# BMW_E34_Touring_Bagage_Light.net
KiCad netlist of a schematic drawn in Altium Designer
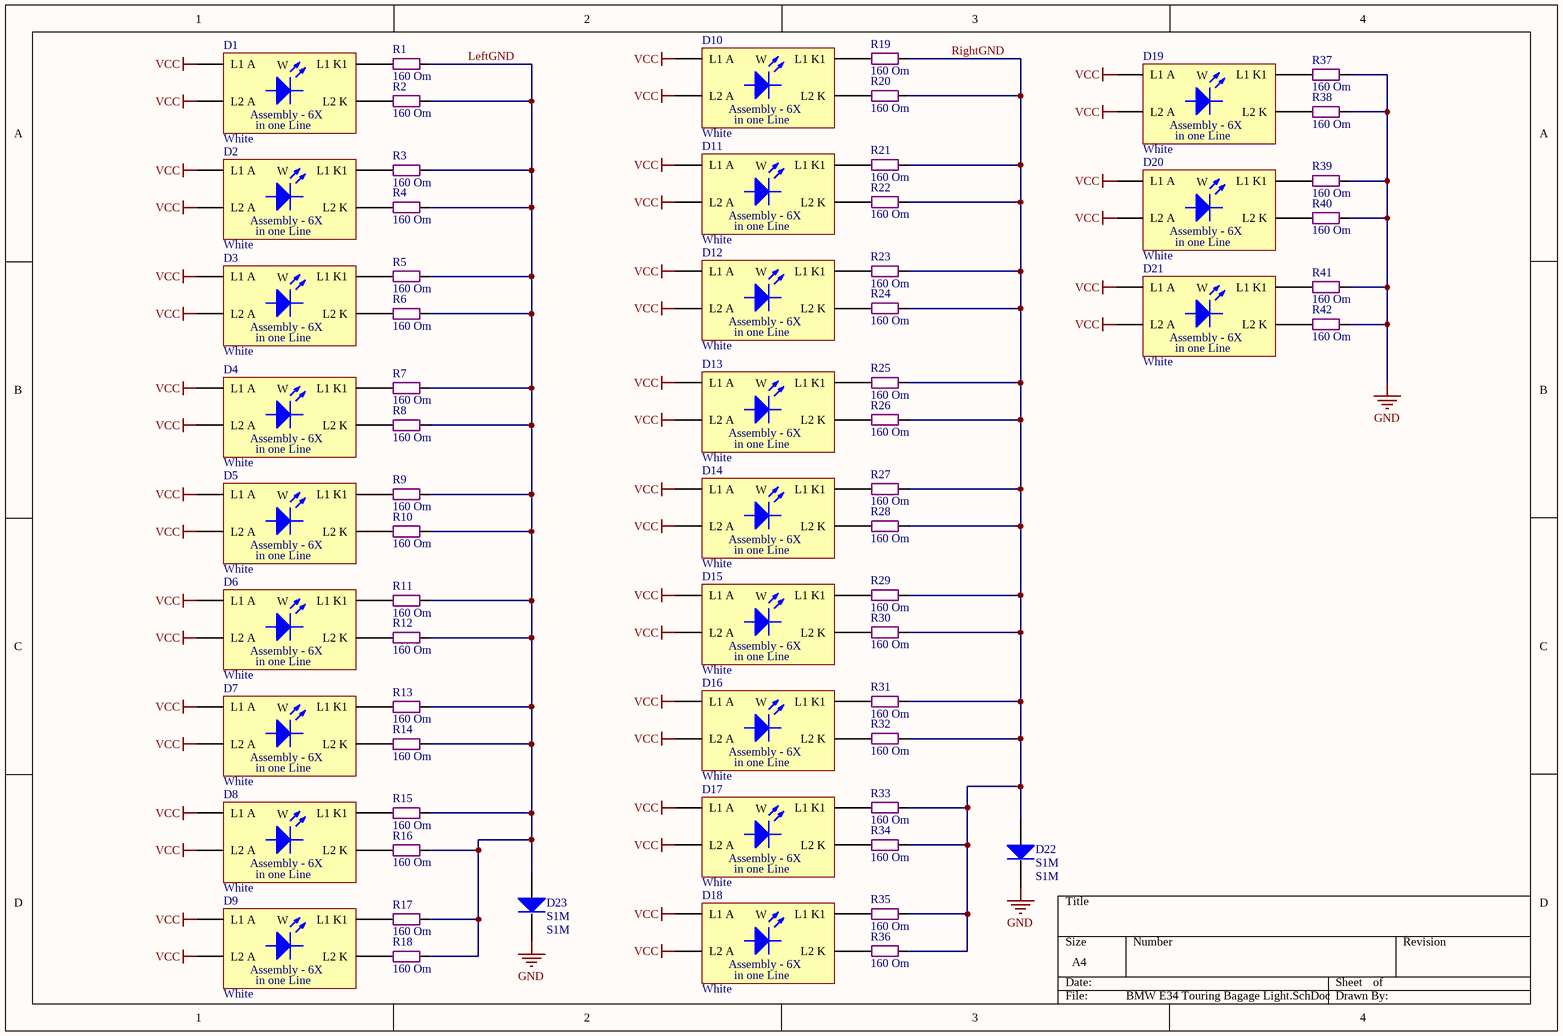
[diagram p0: BMW E34 Touring Bagage Light.SchDoc]

(export (version "E")
  (design (tool "Eeschema 10.0.6"))
  (components
    (comp (ref "D1")
      (value "White")
      (footprint "LED:LED Assembly Round 5mm White 6X 0.5mm")
      (description "3.2-3.4v 25mA, 16-20cd")
      (libsource (lib "LED") (part "Led Assembly Round 5mm White 6X"))
    )
    (comp (ref "D2")
      (value "White")
      (footprint "LED:LED Assembly Round 5mm White 6X 0.5mm")
      (description "3.2-3.4v 25mA, 16-20cd")
      (libsource (lib "LED") (part "Led Assembly Round 5mm White 6X"))
    )
    (comp (ref "D3")
      (value "White")
      (footprint "LED:LED Assembly Round 5mm White 6X 0.5mm")
      (description "3.2-3.4v 25mA, 16-20cd")
      (libsource (lib "LED") (part "Led Assembly Round 5mm White 6X"))
    )
    (comp (ref "D4")
      (value "White")
      (footprint "LED:LED Assembly Round 5mm White 6X 0.5mm")
      (description "3.2-3.4v 25mA, 16-20cd")
      (libsource (lib "LED") (part "Led Assembly Round 5mm White 6X"))
    )
    (comp (ref "D5")
      (value "White")
      (footprint "LED:LED Assembly Round 5mm White 6X")
      (description "3.2-3.4v 25mA, 16-20cd")
      (libsource (lib "LED") (part "Led Assembly Round 5mm White 6X"))
    )
    (comp (ref "D6")
      (value "White")
      (footprint "LED:LED Assembly Round 5mm White 6X")
      (description "3.2-3.4v 25mA, 16-20cd")
      (libsource (lib "LED") (part "Led Assembly Round 5mm White 6X"))
    )
    (comp (ref "D7")
      (value "White")
      (footprint "LED:LED Assembly Round 5mm White 6X 0.5mm")
      (description "3.2-3.4v 25mA, 16-20cd")
      (libsource (lib "LED") (part "Led Assembly Round 5mm White 6X"))
    )
    (comp (ref "D8")
      (value "White")
      (footprint "LED:LED Assembly Round 5mm White 6X 0.5mm")
      (description "3.2-3.4v 25mA, 16-20cd")
      (libsource (lib "LED") (part "Led Assembly Round 5mm White 6X"))
    )
    (comp (ref "D9")
      (value "White")
      (footprint "LED:LED Assembly Round 5mm White 6X 0.5mm")
      (description "3.2-3.4v 25mA, 16-20cd")
      (libsource (lib "LED") (part "Led Assembly Round 5mm White 6X"))
    )
    (comp (ref "D10")
      (value "White")
      (footprint "LED:LED Assembly Round 5mm White 6X 0.5mm")
      (description "3.2-3.4v 25mA, 16-20cd")
      (libsource (lib "LED") (part "Led Assembly Round 5mm White 6X"))
    )
    (comp (ref "D11")
      (value "White")
      (footprint "LED:LED Assembly Round 5mm White 6X 0.5mm")
      (description "3.2-3.4v 25mA, 16-20cd")
      (libsource (lib "LED") (part "Led Assembly Round 5mm White 6X"))
    )
    (comp (ref "D12")
      (value "White")
      (footprint "LED:LED Assembly Round 5mm White 6X 0.5mm")
      (description "3.2-3.4v 25mA, 16-20cd")
      (libsource (lib "LED") (part "Led Assembly Round 5mm White 6X"))
    )
    (comp (ref "D13")
      (value "White")
      (footprint "LED:LED Assembly Round 5mm White 6X")
      (description "3.2-3.4v 25mA, 16-20cd")
      (libsource (lib "LED") (part "Led Assembly Round 5mm White 6X"))
    )
    (comp (ref "D14")
      (value "White")
      (footprint "LED:LED Assembly Round 5mm White 6X")
      (description "3.2-3.4v 25mA, 16-20cd")
      (libsource (lib "LED") (part "Led Assembly Round 5mm White 6X"))
    )
    (comp (ref "D15")
      (value "White")
      (footprint "LED:LED Assembly Round 5mm White 6X 0.5mm")
      (description "3.2-3.4v 25mA, 16-20cd")
      (libsource (lib "LED") (part "Led Assembly Round 5mm White 6X"))
    )
    (comp (ref "D16")
      (value "White")
      (footprint "LED:LED Assembly Round 5mm White 6X 0.5mm")
      (description "3.2-3.4v 25mA, 16-20cd")
      (libsource (lib "LED") (part "Led Assembly Round 5mm White 6X"))
    )
    (comp (ref "D17")
      (value "White")
      (footprint "LED:LED Assembly Round 5mm White 6X 0.5mm")
      (description "3.2-3.4v 25mA, 16-20cd")
      (libsource (lib "LED") (part "Led Assembly Round 5mm White 6X"))
    )
    (comp (ref "D18")
      (value "White")
      (footprint "LED:LED Assembly Round 5mm White 6X 0.5mm")
      (description "3.2-3.4v 25mA, 16-20cd")
      (libsource (lib "LED") (part "Led Assembly Round 5mm White 6X"))
    )
    (comp (ref "D19")
      (value "White")
      (footprint "LED:LED Assembly Round 5mm White 2X3 1mm")
      (description "3.2-3.4v 25mA, 16-20cd")
      (libsource (lib "LED") (part "Led Assembly Round 5mm White 6X"))
    )
    (comp (ref "D20")
      (value "White")
      (footprint "LED:LED Assembly Round 5mm White 2X3 1mm")
      (description "3.2-3.4v 25mA, 16-20cd")
      (libsource (lib "LED") (part "Led Assembly Round 5mm White 6X"))
    )
    (comp (ref "D21")
      (value "White")
      (footprint "LED:LED Assembly Round 5mm White 2X3 1mm")
      (description "3.2-3.4v 25mA, 16-20cd")
      (libsource (lib "LED") (part "Led Assembly Round 5mm White 6X"))
    )
    (comp (ref "D22")
      (value "S1M")
      (footprint "Diodes:DO-214AC")
      (description "1 Amp General Purpose Rectifier")
      (fields (field (name "ALTIUM_VALUE") "S1M"))
      (libsource (lib "Diodes") (part "Diode S1M"))
    )
    (comp (ref "D23")
      (value "S1M")
      (footprint "Diodes:DO-214AC")
      (description "1 Amp General Purpose Rectifier")
      (fields (field (name "ALTIUM_VALUE") "S1M"))
      (libsource (lib "Diodes") (part "Diode S1M"))
    )
    (comp (ref "R1")
      (value "160 Om")
      (footprint "PassiveComponents:SMD 0603 (1608)")
      (libsource (lib "PassiveComponents") (part "Res SMD 0603"))
    )
    (comp (ref "R2")
      (value "160 Om")
      (footprint "PassiveComponents:SMD 0603 (1608)")
      (libsource (lib "PassiveComponents") (part "Res SMD 0603"))
    )
    (comp (ref "R3")
      (value "160 Om")
      (footprint "PassiveComponents:SMD 0603 (1608)")
      (libsource (lib "PassiveComponents") (part "Res SMD 0603"))
    )
    (comp (ref "R4")
      (value "160 Om")
      (footprint "PassiveComponents:SMD 0603 (1608)")
      (libsource (lib "PassiveComponents") (part "Res SMD 0603"))
    )
    (comp (ref "R5")
      (value "160 Om")
      (footprint "PassiveComponents:SMD 0603 (1608)")
      (libsource (lib "PassiveComponents") (part "Res SMD 0603"))
    )
    (comp (ref "R6")
      (value "160 Om")
      (footprint "PassiveComponents:SMD 0603 (1608)")
      (libsource (lib "PassiveComponents") (part "Res SMD 0603"))
    )
    (comp (ref "R7")
      (value "160 Om")
      (footprint "PassiveComponents:SMD 0603 (1608)")
      (libsource (lib "PassiveComponents") (part "Res SMD 0603"))
    )
    (comp (ref "R8")
      (value "160 Om")
      (footprint "PassiveComponents:SMD 0603 (1608)")
      (libsource (lib "PassiveComponents") (part "Res SMD 0603"))
    )
    (comp (ref "R9")
      (value "160 Om")
      (footprint "PassiveComponents:SMD 0603 (1608)")
      (libsource (lib "PassiveComponents") (part "Res SMD 0603"))
    )
    (comp (ref "R10")
      (value "160 Om")
      (footprint "PassiveComponents:SMD 0603 (1608)")
      (libsource (lib "PassiveComponents") (part "Res SMD 0603"))
    )
    (comp (ref "R11")
      (value "160 Om")
      (footprint "PassiveComponents:SMD 0603 (1608)")
      (libsource (lib "PassiveComponents") (part "Res SMD 0603"))
    )
    (comp (ref "R12")
      (value "160 Om")
      (footprint "PassiveComponents:SMD 0603 (1608)")
      (libsource (lib "PassiveComponents") (part "Res SMD 0603"))
    )
    (comp (ref "R13")
      (value "160 Om")
      (footprint "PassiveComponents:SMD 0603 (1608)")
      (libsource (lib "PassiveComponents") (part "Res SMD 0603"))
    )
    (comp (ref "R14")
      (value "160 Om")
      (footprint "PassiveComponents:SMD 0603 (1608)")
      (libsource (lib "PassiveComponents") (part "Res SMD 0603"))
    )
    (comp (ref "R15")
      (value "160 Om")
      (footprint "PassiveComponents:SMD 0603 (1608)")
      (libsource (lib "PassiveComponents") (part "Res SMD 0603"))
    )
    (comp (ref "R16")
      (value "160 Om")
      (footprint "PassiveComponents:SMD 0603 (1608)")
      (libsource (lib "PassiveComponents") (part "Res SMD 0603"))
    )
    (comp (ref "R17")
      (value "160 Om")
      (footprint "PassiveComponents:SMD 0603 (1608)")
      (libsource (lib "PassiveComponents") (part "Res SMD 0603"))
    )
    (comp (ref "R18")
      (value "160 Om")
      (footprint "PassiveComponents:SMD 0603 (1608)")
      (libsource (lib "PassiveComponents") (part "Res SMD 0603"))
    )
    (comp (ref "R19")
      (value "160 Om")
      (footprint "PassiveComponents:SMD 0603 (1608)")
      (libsource (lib "PassiveComponents") (part "Res SMD 0603"))
    )
    (comp (ref "R20")
      (value "160 Om")
      (footprint "PassiveComponents:SMD 0603 (1608)")
      (libsource (lib "PassiveComponents") (part "Res SMD 0603"))
    )
    (comp (ref "R21")
      (value "160 Om")
      (footprint "PassiveComponents:SMD 0603 (1608)")
      (libsource (lib "PassiveComponents") (part "Res SMD 0603"))
    )
    (comp (ref "R22")
      (value "160 Om")
      (footprint "PassiveComponents:SMD 0603 (1608)")
      (libsource (lib "PassiveComponents") (part "Res SMD 0603"))
    )
    (comp (ref "R23")
      (value "160 Om")
      (footprint "PassiveComponents:SMD 0603 (1608)")
      (libsource (lib "PassiveComponents") (part "Res SMD 0603"))
    )
    (comp (ref "R24")
      (value "160 Om")
      (footprint "PassiveComponents:SMD 0603 (1608)")
      (libsource (lib "PassiveComponents") (part "Res SMD 0603"))
    )
    (comp (ref "R25")
      (value "160 Om")
      (footprint "PassiveComponents:SMD 0603 (1608)")
      (libsource (lib "PassiveComponents") (part "Res SMD 0603"))
    )
    (comp (ref "R26")
      (value "160 Om")
      (footprint "PassiveComponents:SMD 0603 (1608)")
      (libsource (lib "PassiveComponents") (part "Res SMD 0603"))
    )
    (comp (ref "R27")
      (value "160 Om")
      (footprint "PassiveComponents:SMD 0603 (1608)")
      (libsource (lib "PassiveComponents") (part "Res SMD 0603"))
    )
    (comp (ref "R28")
      (value "160 Om")
      (footprint "PassiveComponents:SMD 0603 (1608)")
      (libsource (lib "PassiveComponents") (part "Res SMD 0603"))
    )
    (comp (ref "R29")
      (value "160 Om")
      (footprint "PassiveComponents:SMD 0603 (1608)")
      (libsource (lib "PassiveComponents") (part "Res SMD 0603"))
    )
    (comp (ref "R30")
      (value "160 Om")
      (footprint "PassiveComponents:SMD 0603 (1608)")
      (libsource (lib "PassiveComponents") (part "Res SMD 0603"))
    )
    (comp (ref "R31")
      (value "160 Om")
      (footprint "PassiveComponents:SMD 0603 (1608)")
      (libsource (lib "PassiveComponents") (part "Res SMD 0603"))
    )
    (comp (ref "R32")
      (value "160 Om")
      (footprint "PassiveComponents:SMD 0603 (1608)")
      (libsource (lib "PassiveComponents") (part "Res SMD 0603"))
    )
    (comp (ref "R33")
      (value "160 Om")
      (footprint "PassiveComponents:SMD 0603 (1608)")
      (libsource (lib "PassiveComponents") (part "Res SMD 0603"))
    )
    (comp (ref "R34")
      (value "160 Om")
      (footprint "PassiveComponents:SMD 0603 (1608)")
      (libsource (lib "PassiveComponents") (part "Res SMD 0603"))
    )
    (comp (ref "R35")
      (value "160 Om")
      (footprint "PassiveComponents:SMD 0603 (1608)")
      (libsource (lib "PassiveComponents") (part "Res SMD 0603"))
    )
    (comp (ref "R36")
      (value "160 Om")
      (footprint "PassiveComponents:SMD 0603 (1608)")
      (libsource (lib "PassiveComponents") (part "Res SMD 0603"))
    )
    (comp (ref "R37")
      (value "160 Om")
      (footprint "PassiveComponents:SMD 0603 (1608)")
      (libsource (lib "PassiveComponents") (part "Res SMD 0603"))
    )
    (comp (ref "R38")
      (value "160 Om")
      (footprint "PassiveComponents:SMD 0603 (1608)")
      (libsource (lib "PassiveComponents") (part "Res SMD 0603"))
    )
    (comp (ref "R39")
      (value "160 Om")
      (footprint "PassiveComponents:SMD 0603 (1608)")
      (libsource (lib "PassiveComponents") (part "Res SMD 0603"))
    )
    (comp (ref "R40")
      (value "160 Om")
      (footprint "PassiveComponents:SMD 0603 (1608)")
      (libsource (lib "PassiveComponents") (part "Res SMD 0603"))
    )
    (comp (ref "R41")
      (value "160 Om")
      (footprint "PassiveComponents:SMD 0603 (1608)")
      (libsource (lib "PassiveComponents") (part "Res SMD 0603"))
    )
    (comp (ref "R42")
      (value "160 Om")
      (footprint "PassiveComponents:SMD 0603 (1608)")
      (libsource (lib "PassiveComponents") (part "Res SMD 0603"))
    )
  )
  (nets
    (net (code "1") (name "/LeftGND") (class "Default")
      (node (ref "D23") (pin "A") (pinfunction "A_A") (pintype "passive"))
      (node (ref "R1") (pin "2") (pinfunction "2_2") (pintype "passive"))
      (node (ref "R10") (pin "2") (pinfunction "2_2") (pintype "passive"))
      (node (ref "R11") (pin "2") (pinfunction "2_2") (pintype "passive"))
      (node (ref "R12") (pin "2") (pinfunction "2_2") (pintype "passive"))
      (node (ref "R13") (pin "2") (pinfunction "2_2") (pintype "passive"))
      (node (ref "R14") (pin "2") (pinfunction "2_2") (pintype "passive"))
      (node (ref "R15") (pin "2") (pinfunction "2_2") (pintype "passive"))
      (node (ref "R16") (pin "2") (pinfunction "2_2") (pintype "passive"))
      (node (ref "R17") (pin "2") (pinfunction "2_2") (pintype "passive"))
      (node (ref "R18") (pin "2") (pinfunction "2_2") (pintype "passive"))
      (node (ref "R2") (pin "2") (pinfunction "2_2") (pintype "passive"))
      (node (ref "R3") (pin "2") (pinfunction "2_2") (pintype "passive"))
      (node (ref "R4") (pin "2") (pinfunction "2_2") (pintype "passive"))
      (node (ref "R5") (pin "2") (pinfunction "2_2") (pintype "passive"))
      (node (ref "R6") (pin "2") (pinfunction "2_2") (pintype "passive"))
      (node (ref "R7") (pin "2") (pinfunction "2_2") (pintype "passive"))
      (node (ref "R8") (pin "2") (pinfunction "2_2") (pintype "passive"))
      (node (ref "R9") (pin "2") (pinfunction "2_2") (pintype "passive"))
    )
    (net (code "2") (name "/RightGND") (class "Default")
      (node (ref "D22") (pin "A") (pinfunction "A_A") (pintype "passive"))
      (node (ref "R19") (pin "2") (pinfunction "2_2") (pintype "passive"))
      (node (ref "R20") (pin "2") (pinfunction "2_2") (pintype "passive"))
      (node (ref "R21") (pin "2") (pinfunction "2_2") (pintype "passive"))
      (node (ref "R22") (pin "2") (pinfunction "2_2") (pintype "passive"))
      (node (ref "R23") (pin "2") (pinfunction "2_2") (pintype "passive"))
      (node (ref "R24") (pin "2") (pinfunction "2_2") (pintype "passive"))
      (node (ref "R25") (pin "2") (pinfunction "2_2") (pintype "passive"))
      (node (ref "R26") (pin "2") (pinfunction "2_2") (pintype "passive"))
      (node (ref "R27") (pin "2") (pinfunction "2_2") (pintype "passive"))
      (node (ref "R28") (pin "2") (pinfunction "2_2") (pintype "passive"))
      (node (ref "R29") (pin "2") (pinfunction "2_2") (pintype "passive"))
      (node (ref "R30") (pin "2") (pinfunction "2_2") (pintype "passive"))
      (node (ref "R31") (pin "2") (pinfunction "2_2") (pintype "passive"))
      (node (ref "R32") (pin "2") (pinfunction "2_2") (pintype "passive"))
      (node (ref "R33") (pin "2") (pinfunction "2_2") (pintype "passive"))
      (node (ref "R34") (pin "2") (pinfunction "2_2") (pintype "passive"))
      (node (ref "R35") (pin "2") (pinfunction "2_2") (pintype "passive"))
      (node (ref "R36") (pin "2") (pinfunction "2_2") (pintype "passive"))
    )
    (net (code "3") (name "GND") (class "Default")
      (node (ref "D22") (pin "K") (pinfunction "K_K") (pintype "passive"))
      (node (ref "D23") (pin "K") (pinfunction "K_K") (pintype "passive"))
      (node (ref "R37") (pin "2") (pinfunction "2_2") (pintype "passive"))
      (node (ref "R38") (pin "2") (pinfunction "2_2") (pintype "passive"))
      (node (ref "R39") (pin "2") (pinfunction "2_2") (pintype "passive"))
      (node (ref "R40") (pin "2") (pinfunction "2_2") (pintype "passive"))
      (node (ref "R41") (pin "2") (pinfunction "2_2") (pintype "passive"))
      (node (ref "R42") (pin "2") (pinfunction "2_2") (pintype "passive"))
    )
    (net (code "4") (name "Net-(D1-L1_K1)") (class "Default")
      (node (ref "D1") (pin "K1") (pinfunction "L1_K1_K1") (pintype "passive"))
      (node (ref "R1") (pin "1") (pinfunction "1_1") (pintype "passive"))
    )
    (net (code "5") (name "Net-(D1-L2_K)") (class "Default")
      (node (ref "D1") (pin "K2") (pinfunction "L2_K_K2") (pintype "passive"))
      (node (ref "R2") (pin "1") (pinfunction "1_1") (pintype "passive"))
    )
    (net (code "6") (name "Net-(D2-L1_K1)") (class "Default")
      (node (ref "D2") (pin "K1") (pinfunction "L1_K1_K1") (pintype "passive"))
      (node (ref "R3") (pin "1") (pinfunction "1_1") (pintype "passive"))
    )
    (net (code "7") (name "Net-(D2-L2_K)") (class "Default")
      (node (ref "D2") (pin "K2") (pinfunction "L2_K_K2") (pintype "passive"))
      (node (ref "R4") (pin "1") (pinfunction "1_1") (pintype "passive"))
    )
    (net (code "8") (name "Net-(D3-L1_K1)") (class "Default")
      (node (ref "D3") (pin "K1") (pinfunction "L1_K1_K1") (pintype "passive"))
      (node (ref "R5") (pin "1") (pinfunction "1_1") (pintype "passive"))
    )
    (net (code "9") (name "Net-(D3-L2_K)") (class "Default")
      (node (ref "D3") (pin "K2") (pinfunction "L2_K_K2") (pintype "passive"))
      (node (ref "R6") (pin "1") (pinfunction "1_1") (pintype "passive"))
    )
    (net (code "10") (name "Net-(D4-L1_K1)") (class "Default")
      (node (ref "D4") (pin "K1") (pinfunction "L1_K1_K1") (pintype "passive"))
      (node (ref "R7") (pin "1") (pinfunction "1_1") (pintype "passive"))
    )
    (net (code "11") (name "Net-(D4-L2_K)") (class "Default")
      (node (ref "D4") (pin "K2") (pinfunction "L2_K_K2") (pintype "passive"))
      (node (ref "R8") (pin "1") (pinfunction "1_1") (pintype "passive"))
    )
    (net (code "12") (name "Net-(D5-L1_K1)") (class "Default")
      (node (ref "D5") (pin "K1") (pinfunction "L1_K1_K1") (pintype "passive"))
      (node (ref "R9") (pin "1") (pinfunction "1_1") (pintype "passive"))
    )
    (net (code "13") (name "Net-(D5-L2_K)") (class "Default")
      (node (ref "D5") (pin "K2") (pinfunction "L2_K_K2") (pintype "passive"))
      (node (ref "R10") (pin "1") (pinfunction "1_1") (pintype "passive"))
    )
    (net (code "14") (name "Net-(D6-L1_K1)") (class "Default")
      (node (ref "D6") (pin "K1") (pinfunction "L1_K1_K1") (pintype "passive"))
      (node (ref "R11") (pin "1") (pinfunction "1_1") (pintype "passive"))
    )
    (net (code "15") (name "Net-(D6-L2_K)") (class "Default")
      (node (ref "D6") (pin "K2") (pinfunction "L2_K_K2") (pintype "passive"))
      (node (ref "R12") (pin "1") (pinfunction "1_1") (pintype "passive"))
    )
    (net (code "16") (name "Net-(D7-L1_K1)") (class "Default")
      (node (ref "D7") (pin "K1") (pinfunction "L1_K1_K1") (pintype "passive"))
      (node (ref "R13") (pin "1") (pinfunction "1_1") (pintype "passive"))
    )
    (net (code "17") (name "Net-(D7-L2_K)") (class "Default")
      (node (ref "D7") (pin "K2") (pinfunction "L2_K_K2") (pintype "passive"))
      (node (ref "R14") (pin "1") (pinfunction "1_1") (pintype "passive"))
    )
    (net (code "18") (name "Net-(D8-L1_K1)") (class "Default")
      (node (ref "D8") (pin "K1") (pinfunction "L1_K1_K1") (pintype "passive"))
      (node (ref "R15") (pin "1") (pinfunction "1_1") (pintype "passive"))
    )
    (net (code "19") (name "Net-(D8-L2_K)") (class "Default")
      (node (ref "D8") (pin "K2") (pinfunction "L2_K_K2") (pintype "passive"))
      (node (ref "R16") (pin "1") (pinfunction "1_1") (pintype "passive"))
    )
    (net (code "20") (name "Net-(D9-L1_K1)") (class "Default")
      (node (ref "D9") (pin "K1") (pinfunction "L1_K1_K1") (pintype "passive"))
      (node (ref "R17") (pin "1") (pinfunction "1_1") (pintype "passive"))
    )
    (net (code "21") (name "Net-(D9-L2_K)") (class "Default")
      (node (ref "D9") (pin "K2") (pinfunction "L2_K_K2") (pintype "passive"))
      (node (ref "R18") (pin "1") (pinfunction "1_1") (pintype "passive"))
    )
    (net (code "22") (name "Net-(D10-L1_K1)") (class "Default")
      (node (ref "D10") (pin "K1") (pinfunction "L1_K1_K1") (pintype "passive"))
      (node (ref "R19") (pin "1") (pinfunction "1_1") (pintype "passive"))
    )
    (net (code "23") (name "Net-(D10-L2_K)") (class "Default")
      (node (ref "D10") (pin "K2") (pinfunction "L2_K_K2") (pintype "passive"))
      (node (ref "R20") (pin "1") (pinfunction "1_1") (pintype "passive"))
    )
    (net (code "24") (name "Net-(D11-L1_K1)") (class "Default")
      (node (ref "D11") (pin "K1") (pinfunction "L1_K1_K1") (pintype "passive"))
      (node (ref "R21") (pin "1") (pinfunction "1_1") (pintype "passive"))
    )
    (net (code "25") (name "Net-(D11-L2_K)") (class "Default")
      (node (ref "D11") (pin "K2") (pinfunction "L2_K_K2") (pintype "passive"))
      (node (ref "R22") (pin "1") (pinfunction "1_1") (pintype "passive"))
    )
    (net (code "26") (name "Net-(D12-L1_K1)") (class "Default")
      (node (ref "D12") (pin "K1") (pinfunction "L1_K1_K1") (pintype "passive"))
      (node (ref "R23") (pin "1") (pinfunction "1_1") (pintype "passive"))
    )
    (net (code "27") (name "Net-(D12-L2_K)") (class "Default")
      (node (ref "D12") (pin "K2") (pinfunction "L2_K_K2") (pintype "passive"))
      (node (ref "R24") (pin "1") (pinfunction "1_1") (pintype "passive"))
    )
    (net (code "28") (name "Net-(D13-L1_K1)") (class "Default")
      (node (ref "D13") (pin "K1") (pinfunction "L1_K1_K1") (pintype "passive"))
      (node (ref "R25") (pin "1") (pinfunction "1_1") (pintype "passive"))
    )
    (net (code "29") (name "Net-(D13-L2_K)") (class "Default")
      (node (ref "D13") (pin "K2") (pinfunction "L2_K_K2") (pintype "passive"))
      (node (ref "R26") (pin "1") (pinfunction "1_1") (pintype "passive"))
    )
    (net (code "30") (name "Net-(D14-L1_K1)") (class "Default")
      (node (ref "D14") (pin "K1") (pinfunction "L1_K1_K1") (pintype "passive"))
      (node (ref "R27") (pin "1") (pinfunction "1_1") (pintype "passive"))
    )
    (net (code "31") (name "Net-(D14-L2_K)") (class "Default")
      (node (ref "D14") (pin "K2") (pinfunction "L2_K_K2") (pintype "passive"))
      (node (ref "R28") (pin "1") (pinfunction "1_1") (pintype "passive"))
    )
    (net (code "32") (name "Net-(D15-L1_K1)") (class "Default")
      (node (ref "D15") (pin "K1") (pinfunction "L1_K1_K1") (pintype "passive"))
      (node (ref "R29") (pin "1") (pinfunction "1_1") (pintype "passive"))
    )
    (net (code "33") (name "Net-(D15-L2_K)") (class "Default")
      (node (ref "D15") (pin "K2") (pinfunction "L2_K_K2") (pintype "passive"))
      (node (ref "R30") (pin "1") (pinfunction "1_1") (pintype "passive"))
    )
    (net (code "34") (name "Net-(D16-L1_K1)") (class "Default")
      (node (ref "D16") (pin "K1") (pinfunction "L1_K1_K1") (pintype "passive"))
      (node (ref "R31") (pin "1") (pinfunction "1_1") (pintype "passive"))
    )
    (net (code "35") (name "Net-(D16-L2_K)") (class "Default")
      (node (ref "D16") (pin "K2") (pinfunction "L2_K_K2") (pintype "passive"))
      (node (ref "R32") (pin "1") (pinfunction "1_1") (pintype "passive"))
    )
    (net (code "36") (name "Net-(D17-L1_K1)") (class "Default")
      (node (ref "D17") (pin "K1") (pinfunction "L1_K1_K1") (pintype "passive"))
      (node (ref "R33") (pin "1") (pinfunction "1_1") (pintype "passive"))
    )
    (net (code "37") (name "Net-(D17-L2_K)") (class "Default")
      (node (ref "D17") (pin "K2") (pinfunction "L2_K_K2") (pintype "passive"))
      (node (ref "R34") (pin "1") (pinfunction "1_1") (pintype "passive"))
    )
    (net (code "38") (name "Net-(D18-L1_K1)") (class "Default")
      (node (ref "D18") (pin "K1") (pinfunction "L1_K1_K1") (pintype "passive"))
      (node (ref "R35") (pin "1") (pinfunction "1_1") (pintype "passive"))
    )
    (net (code "39") (name "Net-(D18-L2_K)") (class "Default")
      (node (ref "D18") (pin "K2") (pinfunction "L2_K_K2") (pintype "passive"))
      (node (ref "R36") (pin "1") (pinfunction "1_1") (pintype "passive"))
    )
    (net (code "40") (name "Net-(D19-L1_K1)") (class "Default")
      (node (ref "D19") (pin "K1") (pinfunction "L1_K1_K1") (pintype "passive"))
      (node (ref "R37") (pin "1") (pinfunction "1_1") (pintype "passive"))
    )
    (net (code "41") (name "Net-(D19-L2_K)") (class "Default")
      (node (ref "D19") (pin "K2") (pinfunction "L2_K_K2") (pintype "passive"))
      (node (ref "R38") (pin "1") (pinfunction "1_1") (pintype "passive"))
    )
    (net (code "42") (name "Net-(D20-L1_K1)") (class "Default")
      (node (ref "D20") (pin "K1") (pinfunction "L1_K1_K1") (pintype "passive"))
      (node (ref "R39") (pin "1") (pinfunction "1_1") (pintype "passive"))
    )
    (net (code "43") (name "Net-(D20-L2_K)") (class "Default")
      (node (ref "D20") (pin "K2") (pinfunction "L2_K_K2") (pintype "passive"))
      (node (ref "R40") (pin "1") (pinfunction "1_1") (pintype "passive"))
    )
    (net (code "44") (name "Net-(D21-L1_K1)") (class "Default")
      (node (ref "D21") (pin "K1") (pinfunction "L1_K1_K1") (pintype "passive"))
      (node (ref "R41") (pin "1") (pinfunction "1_1") (pintype "passive"))
    )
    (net (code "45") (name "Net-(D21-L2_K)") (class "Default")
      (node (ref "D21") (pin "K2") (pinfunction "L2_K_K2") (pintype "passive"))
      (node (ref "R42") (pin "1") (pinfunction "1_1") (pintype "passive"))
    )
    (net (code "46") (name "VCC") (class "Default")
      (node (ref "D1") (pin "A1") (pinfunction "L1_A_A1") (pintype "passive"))
      (node (ref "D1") (pin "A2") (pinfunction "L2_A_A2") (pintype "passive"))
      (node (ref "D10") (pin "A1") (pinfunction "L1_A_A1") (pintype "passive"))
      (node (ref "D10") (pin "A2") (pinfunction "L2_A_A2") (pintype "passive"))
      (node (ref "D11") (pin "A1") (pinfunction "L1_A_A1") (pintype "passive"))
      (node (ref "D11") (pin "A2") (pinfunction "L2_A_A2") (pintype "passive"))
      (node (ref "D12") (pin "A1") (pinfunction "L1_A_A1") (pintype "passive"))
      (node (ref "D12") (pin "A2") (pinfunction "L2_A_A2") (pintype "passive"))
      (node (ref "D13") (pin "A1") (pinfunction "L1_A_A1") (pintype "passive"))
      (node (ref "D13") (pin "A2") (pinfunction "L2_A_A2") (pintype "passive"))
      (node (ref "D14") (pin "A1") (pinfunction "L1_A_A1") (pintype "passive"))
      (node (ref "D14") (pin "A2") (pinfunction "L2_A_A2") (pintype "passive"))
      (node (ref "D15") (pin "A1") (pinfunction "L1_A_A1") (pintype "passive"))
      (node (ref "D15") (pin "A2") (pinfunction "L2_A_A2") (pintype "passive"))
      (node (ref "D16") (pin "A1") (pinfunction "L1_A_A1") (pintype "passive"))
      (node (ref "D16") (pin "A2") (pinfunction "L2_A_A2") (pintype "passive"))
      (node (ref "D17") (pin "A1") (pinfunction "L1_A_A1") (pintype "passive"))
      (node (ref "D17") (pin "A2") (pinfunction "L2_A_A2") (pintype "passive"))
      (node (ref "D18") (pin "A1") (pinfunction "L1_A_A1") (pintype "passive"))
      (node (ref "D18") (pin "A2") (pinfunction "L2_A_A2") (pintype "passive"))
      (node (ref "D19") (pin "A1") (pinfunction "L1_A_A1") (pintype "passive"))
      (node (ref "D19") (pin "A2") (pinfunction "L2_A_A2") (pintype "passive"))
      (node (ref "D2") (pin "A1") (pinfunction "L1_A_A1") (pintype "passive"))
      (node (ref "D2") (pin "A2") (pinfunction "L2_A_A2") (pintype "passive"))
      (node (ref "D20") (pin "A1") (pinfunction "L1_A_A1") (pintype "passive"))
      (node (ref "D20") (pin "A2") (pinfunction "L2_A_A2") (pintype "passive"))
      (node (ref "D21") (pin "A1") (pinfunction "L1_A_A1") (pintype "passive"))
      (node (ref "D21") (pin "A2") (pinfunction "L2_A_A2") (pintype "passive"))
      (node (ref "D3") (pin "A1") (pinfunction "L1_A_A1") (pintype "passive"))
      (node (ref "D3") (pin "A2") (pinfunction "L2_A_A2") (pintype "passive"))
      (node (ref "D4") (pin "A1") (pinfunction "L1_A_A1") (pintype "passive"))
      (node (ref "D4") (pin "A2") (pinfunction "L2_A_A2") (pintype "passive"))
      (node (ref "D5") (pin "A1") (pinfunction "L1_A_A1") (pintype "passive"))
      (node (ref "D5") (pin "A2") (pinfunction "L2_A_A2") (pintype "passive"))
      (node (ref "D6") (pin "A1") (pinfunction "L1_A_A1") (pintype "passive"))
      (node (ref "D6") (pin "A2") (pinfunction "L2_A_A2") (pintype "passive"))
      (node (ref "D7") (pin "A1") (pinfunction "L1_A_A1") (pintype "passive"))
      (node (ref "D7") (pin "A2") (pinfunction "L2_A_A2") (pintype "passive"))
      (node (ref "D8") (pin "A1") (pinfunction "L1_A_A1") (pintype "passive"))
      (node (ref "D8") (pin "A2") (pinfunction "L2_A_A2") (pintype "passive"))
      (node (ref "D9") (pin "A1") (pinfunction "L1_A_A1") (pintype "passive"))
      (node (ref "D9") (pin "A2") (pinfunction "L2_A_A2") (pintype "passive"))
    )
  )
)
